# accesory.net
KiCad netlist of a schematic drawn in Altium Designer
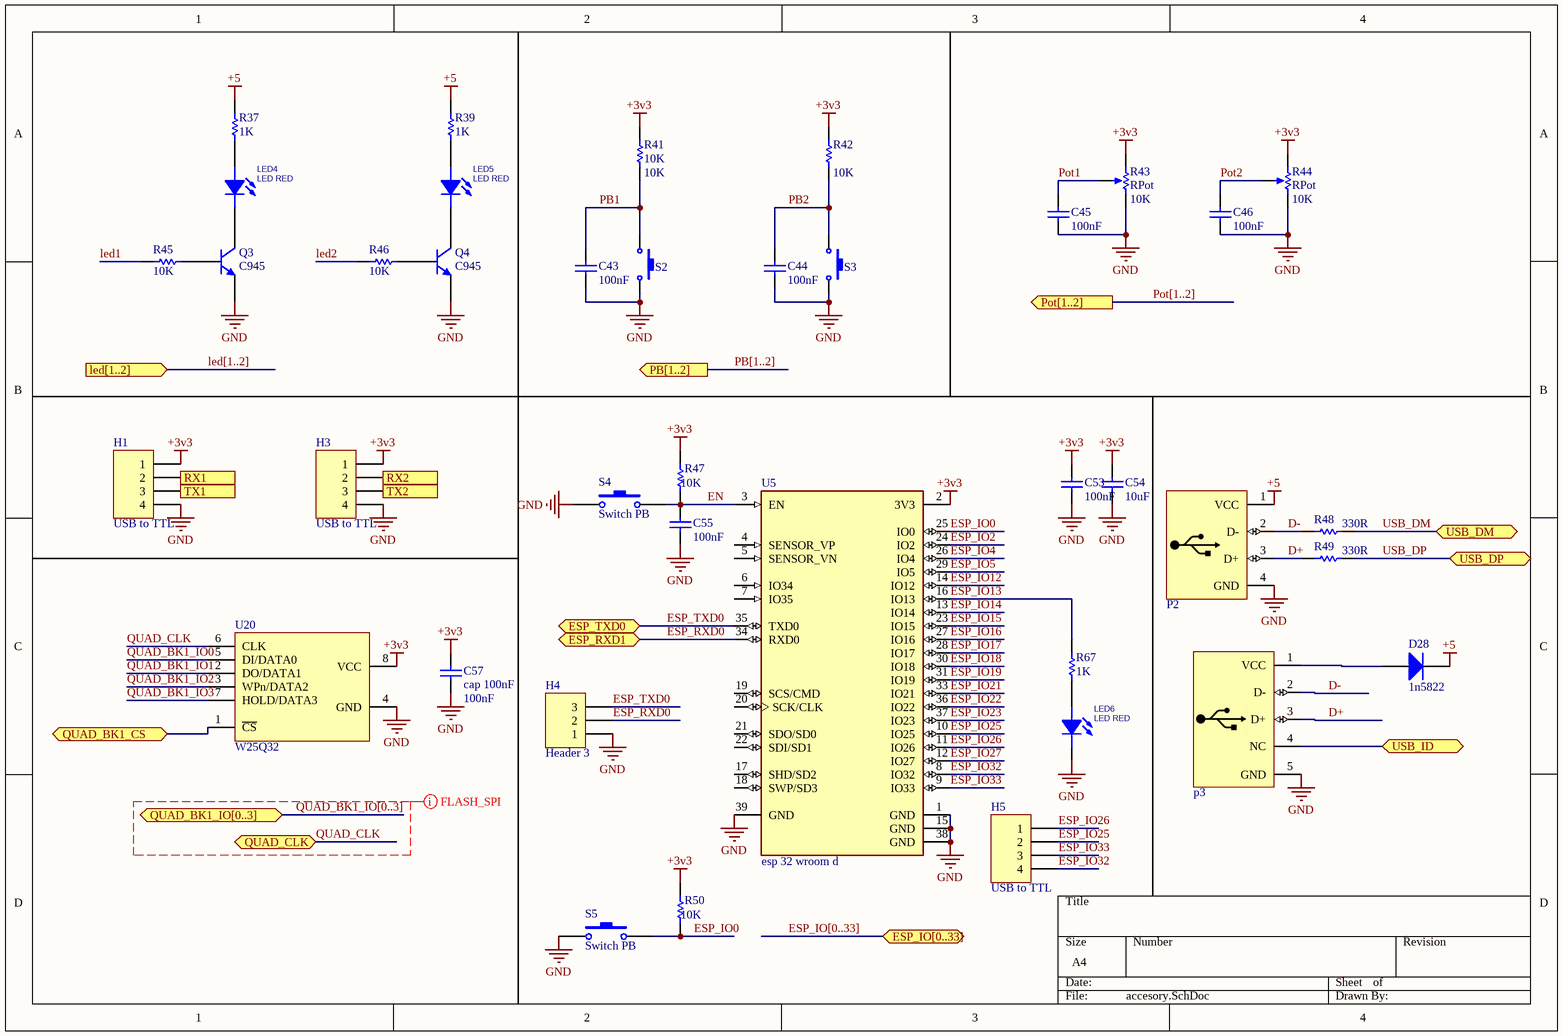
[diagram p0: accesory.SchDoc]

(export (version "E")
  (design (tool "Eeschema 10.0.6"))
  (components
    (comp (ref "C43")
      (value "100nF")
      (footprint "SMD_CAP_0805")
      (description "Capacitor")
      (fields (field (name "PUBLISHER") "Altium Limited"))
      (libsource (lib "Miscellaneous Devices") (part "Cap"))
    )
    (comp (ref "C44")
      (value "100nF")
      (footprint "SMD_CAP_0805")
      (description "Capacitor")
      (fields (field (name "PUBLISHER") "Altium Limited"))
      (libsource (lib "Miscellaneous Devices") (part "Cap"))
    )
    (comp (ref "C45")
      (value "100nF")
      (footprint "SMD_CAP_0805")
      (description "Capacitor")
      (fields (field (name "PUBLISHER") "Altium Limited"))
      (libsource (lib "Miscellaneous Devices") (part "Cap"))
    )
    (comp (ref "C46")
      (value "100nF")
      (footprint "SMD_CAP_0805")
      (description "Capacitor")
      (fields (field (name "PUBLISHER") "Altium Limited"))
      (libsource (lib "Miscellaneous Devices") (part "Cap"))
    )
    (comp (ref "C53")
      (value "100nF")
      (footprint "CAP0805")
      (description "CAP SMD 0805")
      (fields (field (name "PUBLISHER") "Altium Limited"))
      (libsource (lib "Miscellaneous Devices") (part "Cap"))
    )
    (comp (ref "C54")
      (value "10uF")
      (footprint "CAP0805")
      (description "CAP SMD 0805")
      (fields (field (name "PUBLISHER") "Altium Limited"))
      (libsource (lib "Miscellaneous Devices") (part "Cap"))
    )
    (comp (ref "C55")
      (value "100nF")
      (footprint "CAP0805")
      (description "CAP SMD 0805")
      (fields (field (name "PUBLISHER") "Altium Limited"))
      (libsource (lib "Miscellaneous Devices") (part "Cap"))
    )
    (comp (ref "C57")
      (value "cap 100nF")
      (footprint "Cap 805")
      (description "Capacitor")
      (fields (field (name "ALTIUM_VALUE") "100nF") (field (name "PUBLISHER") "Altium Limited"))
      (libsource (lib "Miscellaneous Devices") (part "Cap"))
    )
    (comp (ref "D28")
      (value "1n5822")
      (footprint "DO214AC SMA")
      (description "1 Amp General Purpose Rectifier")
      (fields (field (name "PUBLISHER") "Altium Limited"))
      (libsource (lib "Miscellaneous Devices") (part "Diode 1N4007"))
    )
    (comp (ref "H1")
      (value "USB to TTL")
      (footprint "HDR1X4")
      (libsource (lib "Mine-Discreet") (part "H-1x4"))
    )
    (comp (ref "H3")
      (value "USB to TTL")
      (footprint "HDR1X4")
      (libsource (lib "Mine-Discreet") (part "H-1x4"))
    )
    (comp (ref "H4")
      (value "Header 3")
      (footprint "HDR1X3")
      (description "Header, 3-Pin")
      (fields (field (name "PUBLISHER") "Altium Limited"))
      (libsource (lib "Miscellaneous Connectors") (part "Header 3"))
    )
    (comp (ref "H5")
      (value "USB to TTL")
      (footprint "HDR1X4")
      (libsource (lib "Mine-Discreet") (part "H-1x4"))
    )
    (comp (ref "LED4")
      (value "LED RED")
      (footprint "led_0805")
      (description "Light Emitting Diode")
      (fields (field (name "DESIGNER") "Abbas Basereh"))
      (libsource (lib "Altium (2)") (part "LED 5MM"))
    )
    (comp (ref "LED5")
      (value "LED RED")
      (footprint "led_0805")
      (description "Light Emitting Diode")
      (fields (field (name "DESIGNER") "Abbas Basereh"))
      (libsource (lib "Altium (2)") (part "LED 5MM"))
    )
    (comp (ref "LED6")
      (value "LED RED")
      (footprint "led_0805")
      (description "Light Emitting Diode")
      (fields (field (name "DESIGNER") "Abbas Basereh"))
      (libsource (lib "Altium (2)") (part "LED 5MM"))
    )
    (comp (ref "P2")
      (value "USB Connector")
      (footprint "USB2.5-2H4C")
      (description "USB Connector-A Type")
      (libsource (lib "Altium (2)") (part "USB A-Type"))
    )
    (comp (ref "p3")
      (value "USB Connector")
      (footprint "USB_AB_BM_SHS")
      (description "USB Connector MICRO-B Type")
      (fields (field (name "DESIGNER") "ABBAS BASEREH") (field (name "PUBLISHER") "ABBAS BASEREH"))
      (libsource (lib "Altium (2)") (part "USB MICRO"))
    )
    (comp (ref "Q3")
      (value "C945")
      (footprint "SOT23_N")
      (description "NPN Silicon Epitaxial Planar Transistor")
      (fields (field (name "PUBLISHER") "Abbas Basereh"))
      (libsource (lib "Altium (2)") (part "C945"))
    )
    (comp (ref "Q4")
      (value "C945")
      (footprint "SOT23_N")
      (description "NPN Silicon Epitaxial Planar Transistor")
      (fields (field (name "PUBLISHER") "Abbas Basereh"))
      (libsource (lib "Altium (2)") (part "C945"))
    )
    (comp (ref "R37")
      (value "1K")
      (footprint "RES 0805 (2012X06L)")
      (description "RES Axial 0.25W")
      (fields (field (name "DESIGNER") "Abbas Basereh"))
      (libsource (lib "Altium (2)") (part "RES Axial 0.25W"))
    )
    (comp (ref "R39")
      (value "1K")
      (footprint "RES 0805 (2012X06L)")
      (description "RES Axial 0.25W")
      (fields (field (name "DESIGNER") "Abbas Basereh"))
      (libsource (lib "Altium (2)") (part "RES Axial 0.25W"))
    )
    (comp (ref "R41")
      (value "10K")
      (footprint "RES 0805 (2012X06L)")
      (description "Resistor")
      (fields (field (name "ALTIUM_VALUE") "10K") (field (name "PUBLISHER") "Altium Limited"))
      (libsource (lib "Miscellaneous Devices") (part "Res1"))
    )
    (comp (ref "R42")
      (value "10K")
      (footprint "RES 0805 (2012X06L)")
      (description "Resistor")
      (fields (field (name "PUBLISHER") "Altium Limited"))
      (libsource (lib "Miscellaneous Devices") (part "Res1"))
    )
    (comp (ref "R43")
      (value "RPot")
      (footprint "Multi Turn 02")
      (description "Potentiometer")
      (fields (field (name "ALTIUM_VALUE") "10K") (field (name "PUBLISHER") "Altium Limited"))
      (libsource (lib "Miscellaneous Devices") (part "RPot"))
    )
    (comp (ref "R44")
      (value "RPot")
      (footprint "Multi Turn 02")
      (description "Potentiometer")
      (fields (field (name "ALTIUM_VALUE") "10K") (field (name "PUBLISHER") "Altium Limited"))
      (libsource (lib "Miscellaneous Devices") (part "RPot"))
    )
    (comp (ref "R45")
      (value "10K")
      (footprint "RES 0805 (2012X06L)")
      (description "Resistor")
      (fields (field (name "PUBLISHER") "Altium Limited"))
      (libsource (lib "Miscellaneous Devices") (part "Res1"))
    )
    (comp (ref "R46")
      (value "10K")
      (footprint "RES 0805 (2012X06L)")
      (description "Resistor")
      (fields (field (name "PUBLISHER") "Altium Limited"))
      (libsource (lib "Miscellaneous Devices") (part "Res1"))
    )
    (comp (ref "R47")
      (value "10K")
      (footprint "RES0805")
      (description "Resistor")
      (fields (field (name "PUBLISHER") "Altium Limited"))
      (libsource (lib "Miscellaneous Devices") (part "Res1"))
    )
    (comp (ref "R48")
      (value "330R")
      (footprint "RES 0805 (2012X06L)")
      (description "Resistor")
      (fields (field (name "PUBLISHER") "Altium Limited"))
      (libsource (lib "Miscellaneous Devices") (part "Res1"))
    )
    (comp (ref "R49")
      (value "330R")
      (footprint "RES 0805 (2012X06L)")
      (description "Resistor")
      (fields (field (name "PUBLISHER") "Altium Limited"))
      (libsource (lib "Miscellaneous Devices") (part "Res1"))
    )
    (comp (ref "R50")
      (value "10K")
      (footprint "RES0805")
      (description "Resistor")
      (fields (field (name "PUBLISHER") "Altium Limited"))
      (libsource (lib "Miscellaneous Devices") (part "Res1"))
    )
    (comp (ref "R67")
      (value "1K")
      (footprint "RES 0805 (2012X06L)")
      (description "RES Axial 0.25W")
      (fields (field (name "DESIGNER") "Abbas Basereh"))
      (libsource (lib "Altium (2)") (part "RES Axial 0.25W"))
    )
    (comp (ref "S2")
      (value "Switch PB")
      (footprint "Switch - Push to On")
      (description "Push Button Switch")
      (libsource (lib "Altium (2)") (part "Switch PB"))
    )
    (comp (ref "S3")
      (value "Switch PB")
      (footprint "Switch - Push to On")
      (description "Push Button Switch")
      (libsource (lib "Altium (2)") (part "Switch PB"))
    )
    (comp (ref "S4")
      (value "Switch PB")
      (footprint "Switch - Push to On")
      (description "Push Button Switch")
      (libsource (lib "My Library") (part "Switch PB"))
    )
    (comp (ref "S5")
      (value "Switch PB")
      (footprint "Switch - Push to On")
      (description "Push Button Switch")
      (libsource (lib "My Library") (part "Switch PB"))
    )
    (comp (ref "U5")
      (value "esp 32 wroom d")
      (footprint "esp-wroom")
      (libsource (lib "reciver_sch") (part "ESP32-wroom"))
    )
    (comp (ref "U20")
      (value "W25Q32")
      (footprint "WSON-8x6")
      (description "NOR flash")
      (libsource (lib "ZetaBoard_Lib") (part "W25Q32"))
    )
  )
  (nets
    (net (code "15") (name "+3v3") (class "Default")
      (node (ref "C53") (pin "2") (pinfunction "2_2") (pintype "passive"))
      (node (ref "C54") (pin "2") (pinfunction "2_2") (pintype "passive"))
      (node (ref "C57") (pin "2") (pinfunction "2_2") (pintype "passive"))
      (node (ref "H1") (pin "1") (pinfunction "1_1") (pintype "passive"))
      (node (ref "H3") (pin "1") (pinfunction "1_1") (pintype "passive"))
      (node (ref "R41") (pin "1") (pinfunction "1_1") (pintype "passive"))
      (node (ref "R42") (pin "1") (pinfunction "1_1") (pintype "passive"))
      (node (ref "R43") (pin "1") (pinfunction "TOP_1") (pintype "passive"))
      (node (ref "R44") (pin "1") (pinfunction "TOP_1") (pintype "passive"))
      (node (ref "R47") (pin "1") (pinfunction "1_1") (pintype "passive"))
      (node (ref "R50") (pin "1") (pinfunction "1_1") (pintype "passive"))
      (node (ref "U20") (pin "8") (pinfunction "VCC_8") (pintype "passive"))
      (node (ref "U5") (pin "2") (pinfunction "3V3_2") (pintype "power_in"))
    )
    (net (code "16") (name "+5") (class "Default")
      (node (ref "D28") (pin "2") (pinfunction "K_2") (pintype "passive"))
      (node (ref "P2") (pin "1") (pinfunction "VCC_1") (pintype "power_in"))
      (node (ref "R37") (pin "2") (pinfunction "2_2") (pintype "passive"))
      (node (ref "R39") (pin "2") (pinfunction "2_2") (pintype "passive"))
    )
    (net (code "17") (name "/D+") (class "Default")
      (node (ref "P2") (pin "3") (pinfunction "D+_3") (pintype "bidirectional"))
      (node (ref "R49") (pin "1") (pinfunction "1_1") (pintype "passive"))
      (node (ref "p3") (pin "3") (pinfunction "D+_3") (pintype "bidirectional"))
    )
    (net (code "18") (name "/D-") (class "Default")
      (node (ref "P2") (pin "2") (pinfunction "D-_2") (pintype "bidirectional"))
      (node (ref "R48") (pin "1") (pinfunction "1_1") (pintype "passive"))
      (node (ref "p3") (pin "2") (pinfunction "D-_2") (pintype "bidirectional"))
    )
    (net (code "19") (name "/EN") (class "Default")
      (node (ref "C55") (pin "2") (pinfunction "2_2") (pintype "passive"))
      (node (ref "R47") (pin "2") (pinfunction "2_2") (pintype "passive"))
      (node (ref "S4") (pin "2") (pinfunction "2_2") (pintype "passive"))
      (node (ref "U5") (pin "3") (pinfunction "EN_3") (pintype "input"))
    )
    (net (code "20") (name "/ESP_IO0") (class "Default")
      (node (ref "R50") (pin "2") (pinfunction "2_2") (pintype "passive"))
      (node (ref "S5") (pin "2") (pinfunction "2_2") (pintype "passive"))
      (node (ref "U5") (pin "25") (pinfunction "IO0_25") (pintype "bidirectional"))
    )
    (net (code "21") (name "/ESP_IO2") (class "Default")
      (node (ref "U5") (pin "24") (pinfunction "IO2_24") (pintype "bidirectional"))
    )
    (net (code "22") (name "/ESP_IO4") (class "Default")
      (node (ref "U5") (pin "26") (pinfunction "IO4_26") (pintype "bidirectional"))
    )
    (net (code "23") (name "/ESP_IO5") (class "Default")
      (node (ref "U5") (pin "29") (pinfunction "IO5_29") (pintype "bidirectional"))
    )
    (net (code "24") (name "/ESP_IO12") (class "Default")
      (node (ref "U5") (pin "14") (pinfunction "IO12_14") (pintype "bidirectional"))
    )
    (net (code "25") (name "/ESP_IO13") (class "Default")
      (node (ref "R67") (pin "2") (pinfunction "2_2") (pintype "passive"))
      (node (ref "U5") (pin "16") (pinfunction "IO13_16") (pintype "bidirectional"))
    )
    (net (code "26") (name "/ESP_IO14") (class "Default")
      (node (ref "U5") (pin "13") (pinfunction "IO14_13") (pintype "bidirectional"))
    )
    (net (code "27") (name "/ESP_IO15") (class "Default")
      (node (ref "U5") (pin "23") (pinfunction "IO15_23") (pintype "bidirectional"))
    )
    (net (code "28") (name "/ESP_IO16") (class "Default")
      (node (ref "U5") (pin "27") (pinfunction "IO16_27") (pintype "bidirectional"))
    )
    (net (code "29") (name "/ESP_IO17") (class "Default")
      (node (ref "U5") (pin "28") (pinfunction "IO17_28") (pintype "bidirectional"))
    )
    (net (code "30") (name "/ESP_IO18") (class "Default")
      (node (ref "U5") (pin "30") (pinfunction "IO18_30") (pintype "bidirectional"))
    )
    (net (code "31") (name "/ESP_IO19") (class "Default")
      (node (ref "U5") (pin "31") (pinfunction "IO19_31") (pintype "bidirectional"))
    )
    (net (code "32") (name "/ESP_IO21") (class "Default")
      (node (ref "U5") (pin "33") (pinfunction "IO21_33") (pintype "bidirectional"))
    )
    (net (code "33") (name "/ESP_IO22") (class "Default")
      (node (ref "U5") (pin "36") (pinfunction "IO22_36") (pintype "bidirectional"))
    )
    (net (code "34") (name "/ESP_IO23") (class "Default")
      (node (ref "U5") (pin "37") (pinfunction "IO23_37") (pintype "bidirectional"))
    )
    (net (code "35") (name "/ESP_IO25") (class "Default")
      (node (ref "H5") (pin "2") (pinfunction "2_2") (pintype "passive"))
      (node (ref "U5") (pin "10") (pinfunction "IO25_10") (pintype "bidirectional"))
    )
    (net (code "36") (name "/ESP_IO26") (class "Default")
      (node (ref "H5") (pin "1") (pinfunction "1_1") (pintype "passive"))
      (node (ref "U5") (pin "11") (pinfunction "IO26_11") (pintype "bidirectional"))
    )
    (net (code "37") (name "/ESP_IO27") (class "Default")
      (node (ref "U5") (pin "12") (pinfunction "IO27_12") (pintype "bidirectional"))
    )
    (net (code "38") (name "/ESP_IO32") (class "Default")
      (node (ref "H5") (pin "4") (pinfunction "4_4") (pintype "passive"))
      (node (ref "U5") (pin "8") (pinfunction "IO32_8") (pintype "bidirectional"))
    )
    (net (code "39") (name "/ESP_IO33") (class "Default")
      (node (ref "H5") (pin "3") (pinfunction "3_3") (pintype "passive"))
      (node (ref "U5") (pin "9") (pinfunction "IO33_9") (pintype "bidirectional"))
    )
    (net (code "41") (name "/ESP_RXD0") (class "Default")
      (node (ref "H4") (pin "2") (pinfunction "2_2") (pintype "passive"))
      (node (ref "U5") (pin "34") (pinfunction "RXD0_34") (pintype "bidirectional"))
    )
    (net (code "42") (name "/ESP_TXD0") (class "Default")
      (node (ref "H4") (pin "3") (pinfunction "3_3") (pintype "passive"))
      (node (ref "U5") (pin "35") (pinfunction "TXD0_35") (pintype "bidirectional"))
    )
    (net (code "43") (name "/PB1") (class "Default")
      (node (ref "C43") (pin "2") (pinfunction "2_2") (pintype "passive"))
      (node (ref "R41") (pin "2") (pinfunction "2_2") (pintype "passive"))
      (node (ref "S2") (pin "1") (pinfunction "1_1") (pintype "passive"))
    )
    (net (code "44") (name "/PB2") (class "Default")
      (node (ref "C44") (pin "2") (pinfunction "2_2") (pintype "passive"))
      (node (ref "R42") (pin "2") (pinfunction "2_2") (pintype "passive"))
      (node (ref "S3") (pin "1") (pinfunction "1_1") (pintype "passive"))
    )
    (net (code "46") (name "/Pot1") (class "Default")
      (node (ref "C45") (pin "2") (pinfunction "2_2") (pintype "passive"))
      (node (ref "R43") (pin "3") (pinfunction "TAP_3") (pintype "passive"))
    )
    (net (code "47") (name "/Pot2") (class "Default")
      (node (ref "C46") (pin "2") (pinfunction "2_2") (pintype "passive"))
      (node (ref "R44") (pin "3") (pinfunction "TAP_3") (pintype "passive"))
    )
    (net (code "49") (name "/QUAD_BK1_CS") (class "Default")
      (node (ref "U20") (pin "1") (pinfunction "~{CS}_1") (pintype "passive"))
    )
    (net (code "50") (name "/QUAD_BK1_IO0") (class "Default")
      (node (ref "U20") (pin "5") (pinfunction "DI/DATA0_5") (pintype "passive"))
    )
    (net (code "51") (name "/QUAD_BK1_IO1") (class "Default")
      (node (ref "U20") (pin "2") (pinfunction "DO/DATA1_2") (pintype "passive"))
    )
    (net (code "52") (name "/QUAD_BK1_IO2") (class "Default")
      (node (ref "U20") (pin "3") (pinfunction "WPn/DATA2_3") (pintype "passive"))
    )
    (net (code "53") (name "/QUAD_BK1_IO3") (class "Default")
      (node (ref "U20") (pin "7") (pinfunction "HOLD/DATA3_7") (pintype "passive"))
    )
    (net (code "55") (name "/QUAD_CLK") (class "Default")
      (node (ref "U20") (pin "6") (pinfunction "CLK_6") (pintype "passive"))
    )
    (net (code "56") (name "/RX1") (class "Default")
      (node (ref "H1") (pin "2") (pinfunction "2_2") (pintype "passive"))
    )
    (net (code "57") (name "/RX2") (class "Default")
      (node (ref "H3") (pin "2") (pinfunction "2_2") (pintype "passive"))
    )
    (net (code "58") (name "/TX1") (class "Default")
      (node (ref "H1") (pin "3") (pinfunction "3_3") (pintype "passive"))
    )
    (net (code "59") (name "/TX2") (class "Default")
      (node (ref "H3") (pin "3") (pinfunction "3_3") (pintype "passive"))
    )
    (net (code "60") (name "/USB_DM") (class "Default")
      (node (ref "R48") (pin "2") (pinfunction "2_2") (pintype "passive"))
    )
    (net (code "61") (name "/USB_DP") (class "Default")
      (node (ref "R49") (pin "2") (pinfunction "2_2") (pintype "passive"))
    )
    (net (code "62") (name "/USB_ID") (class "Default")
      (node (ref "p3") (pin "4") (pinfunction "NC_4") (pintype "passive"))
    )
    (net (code "63") (name "/led1") (class "Default")
      (node (ref "R45") (pin "1") (pinfunction "1_1") (pintype "passive"))
    )
    (net (code "64") (name "/led2") (class "Default")
      (node (ref "R46") (pin "1") (pinfunction "1_1") (pintype "passive"))
    )
    (net (code "66") (name "GND") (class "Default")
      (node (ref "C43") (pin "1") (pinfunction "1_1") (pintype "passive"))
      (node (ref "C44") (pin "1") (pinfunction "1_1") (pintype "passive"))
      (node (ref "C45") (pin "1") (pinfunction "1_1") (pintype "passive"))
      (node (ref "C46") (pin "1") (pinfunction "1_1") (pintype "passive"))
      (node (ref "C53") (pin "1") (pinfunction "1_1") (pintype "passive"))
      (node (ref "C54") (pin "1") (pinfunction "1_1") (pintype "passive"))
      (node (ref "C55") (pin "1") (pinfunction "1_1") (pintype "passive"))
      (node (ref "C57") (pin "1") (pinfunction "1_1") (pintype "passive"))
      (node (ref "H1") (pin "4") (pinfunction "4_4") (pintype "passive"))
      (node (ref "H3") (pin "4") (pinfunction "4_4") (pintype "passive"))
      (node (ref "H4") (pin "1") (pinfunction "1_1") (pintype "passive"))
      (node (ref "LED6") (pin "2") (pinfunction "CATHODE_2") (pintype "passive"))
      (node (ref "P2") (pin "4") (pinfunction "GND_4") (pintype "power_in"))
      (node (ref "Q3") (pin "2") (pinfunction "E_2") (pintype "passive"))
      (node (ref "Q4") (pin "2") (pinfunction "E_2") (pintype "passive"))
      (node (ref "R43") (pin "2") (pinfunction "BOT_2") (pintype "passive"))
      (node (ref "R44") (pin "2") (pinfunction "BOT_2") (pintype "passive"))
      (node (ref "S2") (pin "2") (pinfunction "2_2") (pintype "passive"))
      (node (ref "S3") (pin "2") (pinfunction "2_2") (pintype "passive"))
      (node (ref "S4") (pin "1") (pinfunction "1_1") (pintype "passive"))
      (node (ref "S5") (pin "1") (pinfunction "1_1") (pintype "passive"))
      (node (ref "U20") (pin "4") (pinfunction "GND_4") (pintype "passive"))
      (node (ref "U5") (pin "1") (pinfunction "GND_1") (pintype "power_in"))
      (node (ref "U5") (pin "15") (pinfunction "GND_15") (pintype "power_in"))
      (node (ref "U5") (pin "38") (pinfunction "GND_38") (pintype "power_in"))
      (node (ref "U5") (pin "39") (pinfunction "GND_39") (pintype "power_in"))
      (node (ref "p3") (pin "5") (pinfunction "GND_5") (pintype "power_in"))
    )
    (net (code "67") (name "Net-(D28-A)") (class "Default")
      (node (ref "D28") (pin "1") (pinfunction "A_1") (pintype "passive"))
      (node (ref "p3") (pin "1") (pinfunction "VCC_1") (pintype "power_in"))
    )
    (net (code "68") (name "Net-(LED4-ANODE)") (class "Default")
      (node (ref "LED4") (pin "1") (pinfunction "ANODE_1") (pintype "passive"))
      (node (ref "R37") (pin "1") (pinfunction "1_1") (pintype "passive"))
    )
    (net (code "69") (name "Net-(LED4-CATHODE)") (class "Default")
      (node (ref "LED4") (pin "2") (pinfunction "CATHODE_2") (pintype "passive"))
      (node (ref "Q3") (pin "3") (pinfunction "C_3") (pintype "passive"))
    )
    (net (code "70") (name "Net-(LED5-ANODE)") (class "Default")
      (node (ref "LED5") (pin "1") (pinfunction "ANODE_1") (pintype "passive"))
      (node (ref "R39") (pin "1") (pinfunction "1_1") (pintype "passive"))
    )
    (net (code "71") (name "Net-(LED5-CATHODE)") (class "Default")
      (node (ref "LED5") (pin "2") (pinfunction "CATHODE_2") (pintype "passive"))
      (node (ref "Q4") (pin "3") (pinfunction "C_3") (pintype "passive"))
    )
    (net (code "72") (name "Net-(LED6-ANODE)") (class "Default")
      (node (ref "LED6") (pin "1") (pinfunction "ANODE_1") (pintype "passive"))
      (node (ref "R67") (pin "1") (pinfunction "1_1") (pintype "passive"))
    )
    (net (code "73") (name "Net-(Q3-B)") (class "Default")
      (node (ref "Q3") (pin "1") (pinfunction "B_1") (pintype "passive"))
      (node (ref "R45") (pin "2") (pinfunction "2_2") (pintype "passive"))
    )
    (net (code "74") (name "Net-(Q4-B)") (class "Default")
      (node (ref "Q4") (pin "1") (pinfunction "B_1") (pintype "passive"))
      (node (ref "R46") (pin "2") (pinfunction "2_2") (pintype "passive"))
    )
    (net (code "75") (name "unconnected-(U5-IO34-Pad6)") (class "Default")
      (node (ref "U5") (pin "6") (pinfunction "IO34_6") (pintype "input"))
    )
    (net (code "76") (name "unconnected-(U5-IO35-Pad7)") (class "Default")
      (node (ref "U5") (pin "7") (pinfunction "IO35_7") (pintype "input"))
    )
    (net (code "77") (name "unconnected-(U5-SCK{slash}CLK-Pad20)") (class "Default")
      (node (ref "U5") (pin "20") (pinfunction "SCK/CLK_20") (pintype "bidirectional"))
    )
    (net (code "78") (name "unconnected-(U5-SCS{slash}CMD-Pad19)") (class "Default")
      (node (ref "U5") (pin "19") (pinfunction "SCS/CMD_19") (pintype "bidirectional"))
    )
    (net (code "79") (name "unconnected-(U5-SDI{slash}SD1-Pad22)") (class "Default")
      (node (ref "U5") (pin "22") (pinfunction "SDI/SD1_22") (pintype "bidirectional"))
    )
    (net (code "80") (name "unconnected-(U5-SDO{slash}SD0-Pad21)") (class "Default")
      (node (ref "U5") (pin "21") (pinfunction "SDO/SD0_21") (pintype "bidirectional"))
    )
    (net (code "81") (name "unconnected-(U5-SENSOR_VN-Pad5)") (class "Default")
      (node (ref "U5") (pin "5") (pinfunction "SENSOR_VN_5") (pintype "input"))
    )
    (net (code "82") (name "unconnected-(U5-SENSOR_VP-Pad4)") (class "Default")
      (node (ref "U5") (pin "4") (pinfunction "SENSOR_VP_4") (pintype "input"))
    )
    (net (code "83") (name "unconnected-(U5-SHD{slash}SD2-Pad17)") (class "Default")
      (node (ref "U5") (pin "17") (pinfunction "SHD/SD2_17") (pintype "bidirectional"))
    )
    (net (code "84") (name "unconnected-(U5-SWP{slash}SD3-Pad18)") (class "Default")
      (node (ref "U5") (pin "18") (pinfunction "SWP/SD3_18") (pintype "bidirectional"))
    )
  )
)
